# Oldest_Schematic.net
KiCad netlist of a schematic drawn in EAGLE
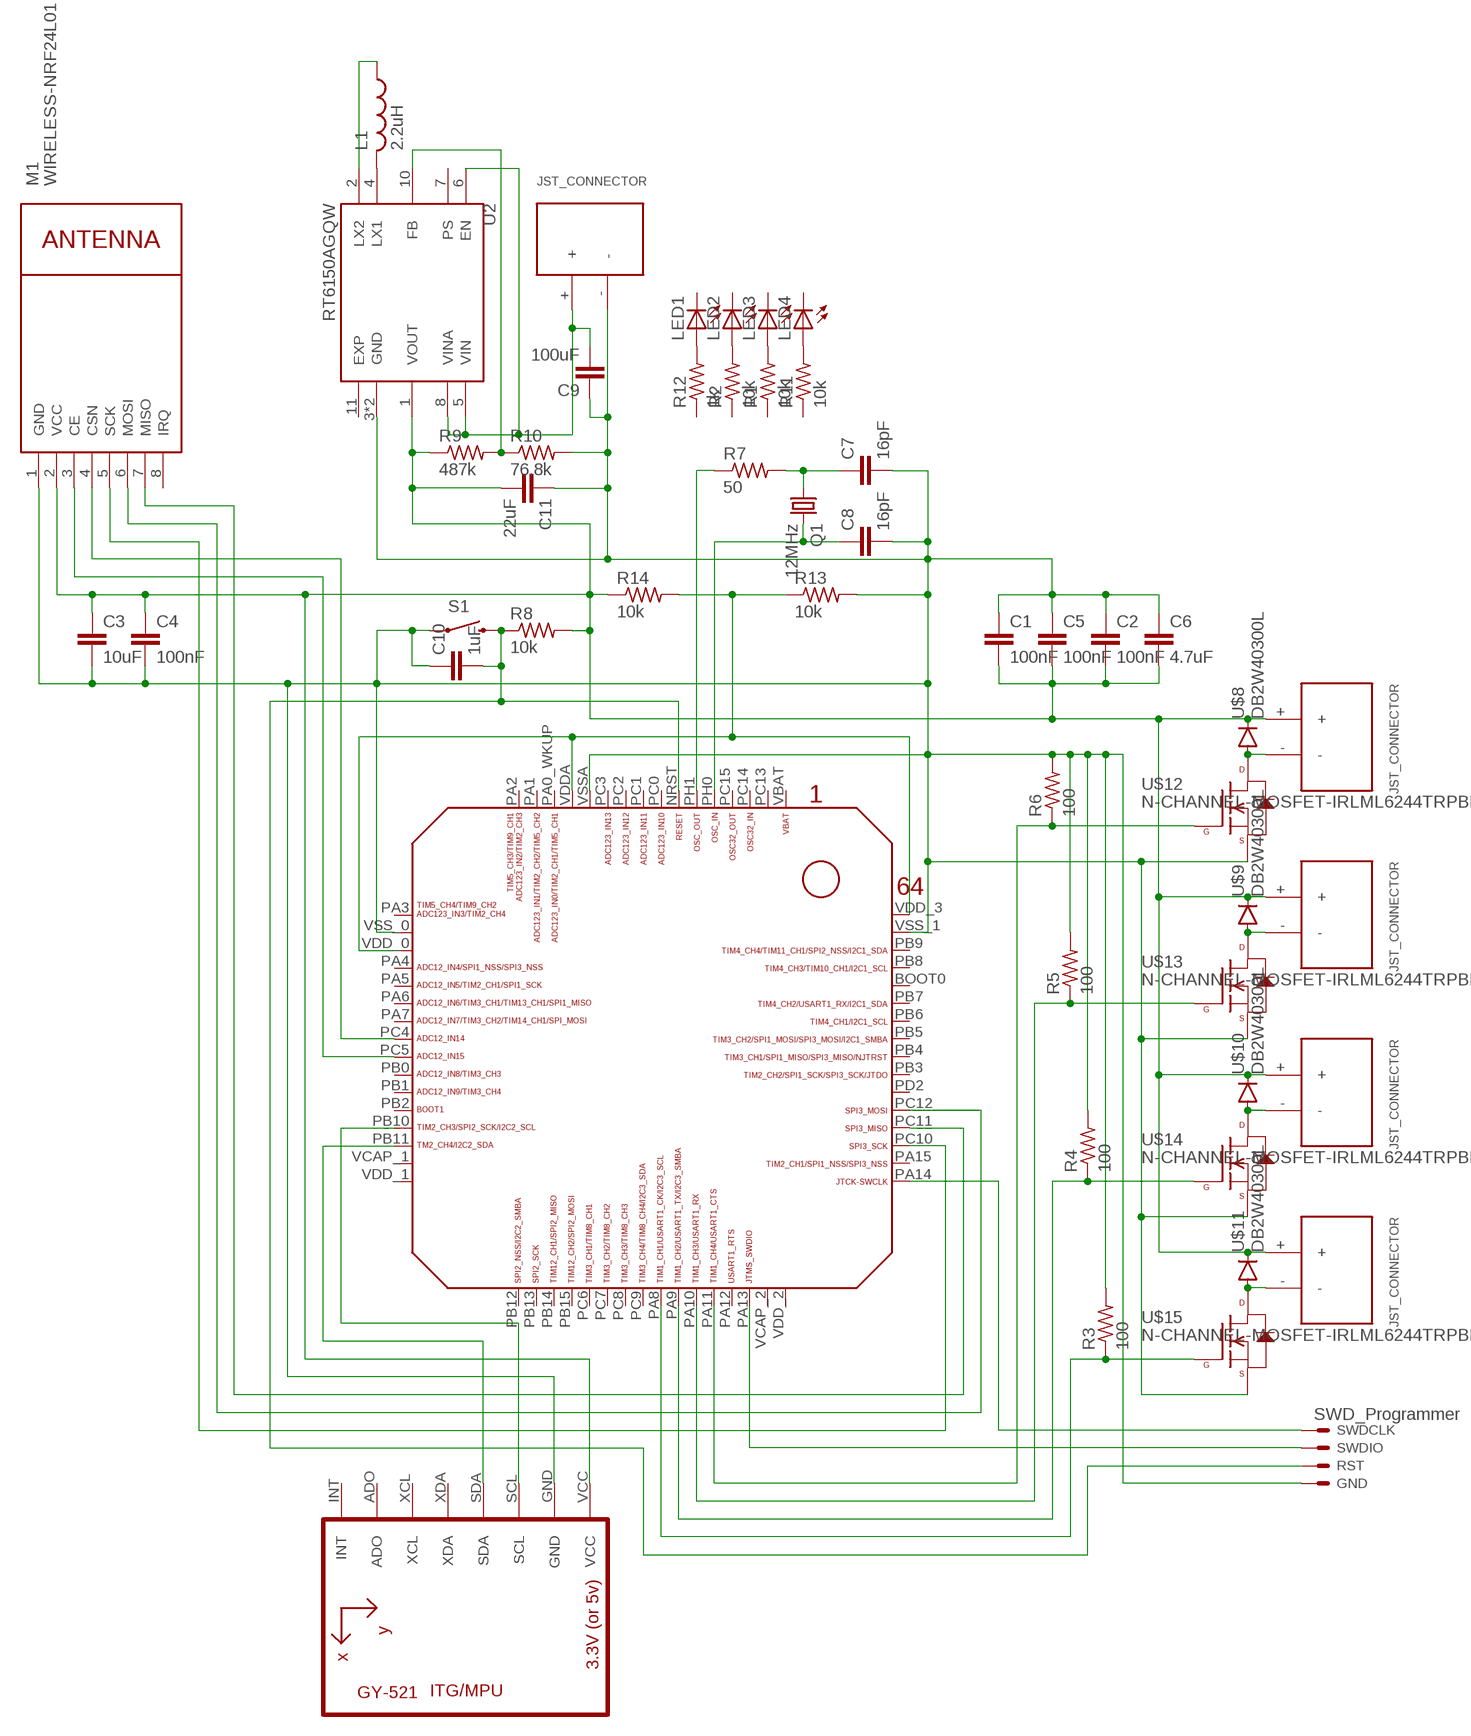
[diagram p0: schematic, sheet 1]

(export (version "E")
  (design (tool "Eeschema 10.0.6"))
  (components
    (comp (ref "C1")
      (value "100nF")
      (footprint "eagle-import:C0603")
      (libsource (lib "eagle-import") (part "C-EUC0603"))
    )
    (comp (ref "C2")
      (value "100nF")
      (footprint "eagle-import:C0603")
      (libsource (lib "eagle-import") (part "C-EUC0603"))
    )
    (comp (ref "C3")
      (value "10uF")
      (footprint "eagle-import:C0603")
      (libsource (lib "eagle-import") (part "C-EUC0603"))
    )
    (comp (ref "C4")
      (value "100nF")
      (footprint "eagle-import:C0603")
      (libsource (lib "eagle-import") (part "C-EUC0603"))
    )
    (comp (ref "C5")
      (value "100nF")
      (footprint "eagle-import:C0603")
      (libsource (lib "eagle-import") (part "C-EUC0603"))
    )
    (comp (ref "C6")
      (value "4.7uF")
      (footprint "eagle-import:C0603")
      (libsource (lib "eagle-import") (part "C-EUC0603"))
    )
    (comp (ref "C7")
      (value "16pF")
      (footprint "eagle-import:C0603")
      (libsource (lib "eagle-import") (part "C-EUC0603"))
    )
    (comp (ref "C8")
      (value "16pF")
      (footprint "eagle-import:C0603")
      (libsource (lib "eagle-import") (part "C-EUC0603"))
    )
    (comp (ref "C9")
      (value "100uF")
      (footprint "eagle-import:C1206")
      (libsource (lib "eagle-import") (part "C-EUC1206"))
    )
    (comp (ref "C10")
      (value "1uF")
      (footprint "eagle-import:C0603")
      (libsource (lib "eagle-import") (part "C-EUC0603"))
    )
    (comp (ref "C11")
      (value "22uF")
      (footprint "eagle-import:C0603")
      (libsource (lib "eagle-import") (part "C-EUC0603"))
    )
    (comp (ref "L1")
      (value "2.2uH")
      (footprint "eagle-import:L0603")
      (libsource (lib "eagle-import") (part "L-USL0603"))
    )
    (comp (ref "LED1")
      (value "LEDSML0603")
      (footprint "eagle-import:SML0603")
      (libsource (lib "eagle-import") (part "LEDSML0603"))
    )
    (comp (ref "LED2")
      (value "LEDSML0603")
      (footprint "eagle-import:SML0603")
      (libsource (lib "eagle-import") (part "LEDSML0603"))
    )
    (comp (ref "LED3")
      (value "LEDSML0603")
      (footprint "eagle-import:SML0603")
      (libsource (lib "eagle-import") (part "LEDSML0603"))
    )
    (comp (ref "LED4")
      (value "LEDSML0603")
      (footprint "eagle-import:SML0603")
      (libsource (lib "eagle-import") (part "LEDSML0603"))
    )
    (comp (ref "M1")
      (value "WIRELESS-NRF24L01")
      (footprint "eagle-import:WIRELESS-NRF24L01")
      (libsource (lib "eagle-import") (part "WIRELESS-NRF24L01"))
    )
    (comp (ref "PIN")
      (value "SWD_Programmer")
      (footprint "eagle-import:53261-04")
      (fields (field (name "MF") "MOLEX"))
      (libsource (lib "eagle-import") (part "53?-04261"))
    )
    (comp (ref "Q1")
      (value "12MHz")
      (footprint "eagle-import:HC49UP")
      (libsource (lib "eagle-import") (part "CRYSTALHC49UP"))
    )
    (comp (ref "R1")
      (value "10k")
      (footprint "eagle-import:R0603")
      (libsource (lib "eagle-import") (part "R-US_R0603"))
    )
    (comp (ref "R2")
      (value "10k")
      (footprint "eagle-import:R0603")
      (libsource (lib "eagle-import") (part "R-US_R0603"))
    )
    (comp (ref "R3")
      (value "100")
      (footprint "eagle-import:R0603")
      (libsource (lib "eagle-import") (part "R-US_R0603"))
    )
    (comp (ref "R4")
      (value "100")
      (footprint "eagle-import:R0603")
      (libsource (lib "eagle-import") (part "R-US_R0603"))
    )
    (comp (ref "R5")
      (value "100")
      (footprint "eagle-import:R0603")
      (libsource (lib "eagle-import") (part "R-US_R0603"))
    )
    (comp (ref "R6")
      (value "100")
      (footprint "eagle-import:R0603")
      (libsource (lib "eagle-import") (part "R-US_R0603"))
    )
    (comp (ref "R7")
      (value "50")
      (footprint "eagle-import:R0603")
      (libsource (lib "eagle-import") (part "R-US_R0603"))
    )
    (comp (ref "R8")
      (value "10k")
      (footprint "eagle-import:R0603")
      (libsource (lib "eagle-import") (part "R-US_R0603"))
    )
    (comp (ref "R9")
      (value "487k")
      (footprint "eagle-import:R0603")
      (libsource (lib "eagle-import") (part "R-US_R0603"))
    )
    (comp (ref "R10")
      (value "76.8k")
      (footprint "eagle-import:R0603")
      (libsource (lib "eagle-import") (part "R-US_R0603"))
    )
    (comp (ref "R11")
      (value "10k")
      (footprint "eagle-import:R0603")
      (libsource (lib "eagle-import") (part "R-US_R0603"))
    )
    (comp (ref "R12")
      (value "1k")
      (footprint "eagle-import:R0603")
      (libsource (lib "eagle-import") (part "R-US_R0603"))
    )
    (comp (ref "R13")
      (value "10k")
      (footprint "eagle-import:R0603")
      (libsource (lib "eagle-import") (part "R-US_R0603"))
    )
    (comp (ref "R14")
      (value "10k")
      (footprint "eagle-import:R0603")
      (libsource (lib "eagle-import") (part "R-US_R0603"))
    )
    (comp (ref "S1")
      (value "SWITCH-MOMENTARY-2SMD")
      (footprint "eagle-import:TACTILE-SWITCH-SMD")
      (libsource (lib "eagle-import") (part "SWITCH-MOMENTARY-2SMD"))
    )
    (comp (ref "U$1")
      (value "STM32F405/415_LQFP64")
      (footprint "eagle-import:STM32F405_415_LQFP64")
      (libsource (lib "eagle-import") (part "STM32F405/415_LQFP64"))
    )
    (comp (ref "U$2")
      (value "JST_CONNECTOR_FEMALE")
      (footprint "eagle-import:JST_CONNECTOR_FEMALE")
      (libsource (lib "eagle-import") (part "JST_CONNECTOR_FEMALE"))
    )
    (comp (ref "U$4")
      (value "JST_CONNECTOR_FEMALE")
      (footprint "eagle-import:JST_CONNECTOR_FEMALE")
      (libsource (lib "eagle-import") (part "JST_CONNECTOR_FEMALE"))
    )
    (comp (ref "U$5")
      (value "JST_CONNECTOR_FEMALE")
      (footprint "eagle-import:JST_CONNECTOR_FEMALE")
      (libsource (lib "eagle-import") (part "JST_CONNECTOR_FEMALE"))
    )
    (comp (ref "U$6")
      (value "JST_CONNECTOR_FEMALE")
      (footprint "eagle-import:JST_CONNECTOR_FEMALE")
      (libsource (lib "eagle-import") (part "JST_CONNECTOR_FEMALE"))
    )
    (comp (ref "U$7")
      (value "JST_CONNECTOR_FEMALE")
      (footprint "eagle-import:JST_CONNECTOR_FEMALE")
      (libsource (lib "eagle-import") (part "JST_CONNECTOR_FEMALE"))
    )
    (comp (ref "U$8")
      (value "DB2W40300L")
      (footprint "eagle-import:MINI2-F3-B")
      (libsource (lib "eagle-import") (part "DB2W40300L"))
    )
    (comp (ref "U$9")
      (value "DB2W40300L")
      (footprint "eagle-import:MINI2-F3-B")
      (libsource (lib "eagle-import") (part "DB2W40300L"))
    )
    (comp (ref "U$10")
      (value "DB2W40300L")
      (footprint "eagle-import:MINI2-F3-B")
      (libsource (lib "eagle-import") (part "DB2W40300L"))
    )
    (comp (ref "U$11")
      (value "DB2W40300L")
      (footprint "eagle-import:MINI2-F3-B")
      (libsource (lib "eagle-import") (part "DB2W40300L"))
    )
    (comp (ref "U$12")
      (value "N-CHANNEL-MOSFET-IRLML6244TRPBF")
      (footprint "eagle-import:SOT23-3")
      (libsource (lib "eagle-import") (part "N-CHANNEL-MOSFET-IRLML6244TRPBF"))
    )
    (comp (ref "U$13")
      (value "N-CHANNEL-MOSFET-IRLML6244TRPBF")
      (footprint "eagle-import:SOT23-3")
      (libsource (lib "eagle-import") (part "N-CHANNEL-MOSFET-IRLML6244TRPBF"))
    )
    (comp (ref "U$14")
      (value "N-CHANNEL-MOSFET-IRLML6244TRPBF")
      (footprint "eagle-import:SOT23-3")
      (libsource (lib "eagle-import") (part "N-CHANNEL-MOSFET-IRLML6244TRPBF"))
    )
    (comp (ref "U$15")
      (value "N-CHANNEL-MOSFET-IRLML6244TRPBF")
      (footprint "eagle-import:SOT23-3")
      (libsource (lib "eagle-import") (part "N-CHANNEL-MOSFET-IRLML6244TRPBF"))
    )
    (comp (ref "U1")
      (value "GY-521MPU6050")
      (footprint "eagle-import:GY-521")
      (libsource (lib "eagle-import") (part "GY-521MPU6050"))
    )
    (comp (ref "U2")
      (value "RT6150AGQW")
      (footprint "eagle-import:SON50P250X250X80-11N")
      (fields (field (name "MF") "Richtek USA"))
      (libsource (lib "eagle-import") (part "RT6150AGQW"))
    )
  )
  (nets
    (net (code "1") (name "Net-(C7-Pad1)") (class "Default")
      (node (ref "C7") (pin "1") (pinfunction "1_1") (pintype "passive"))
      (node (ref "Q1") (pin "1") (pinfunction "1_1") (pintype "passive"))
      (node (ref "R7") (pin "2") (pinfunction "2_2") (pintype "passive"))
    )
    (net (code "2") (name "Net-(C8-Pad1)") (class "Default")
      (node (ref "C8") (pin "1") (pinfunction "1_1") (pintype "passive"))
      (node (ref "Q1") (pin "2") (pinfunction "2_2") (pintype "passive"))
      (node (ref "U$1") (pin "PH0") (pinfunction "PH0_PH0") (pintype "bidirectional"))
    )
    (net (code "3") (name "Net-(LED1-PadA)") (class "Default")
      (node (ref "LED1") (pin "A") (pinfunction "A_A") (pintype "passive"))
      (node (ref "R12") (pin "2") (pinfunction "2_2") (pintype "passive"))
    )
    (net (code "4") (name "Net-(LED2-PadA)") (class "Default")
      (node (ref "LED2") (pin "A") (pinfunction "A_A") (pintype "passive"))
      (node (ref "R2") (pin "2") (pinfunction "2_2") (pintype "passive"))
    )
    (net (code "5") (name "Net-(LED3-PadA)") (class "Default")
      (node (ref "LED3") (pin "A") (pinfunction "A_A") (pintype "passive"))
      (node (ref "R1") (pin "2") (pinfunction "2_2") (pintype "passive"))
    )
    (net (code "6") (name "Net-(LED4-PadA)") (class "Default")
      (node (ref "LED4") (pin "A") (pinfunction "A_A") (pintype "passive"))
      (node (ref "R11") (pin "2") (pinfunction "2_2") (pintype "passive"))
    )
    (net (code "7") (name "Net-(M1-CE)") (class "Default")
      (node (ref "M1") (pin "3") (pinfunction "CE_3") (pintype "bidirectional"))
      (node (ref "U$1") (pin "PC5") (pinfunction "PC5_PC5") (pintype "bidirectional"))
    )
    (net (code "8") (name "Net-(M1-CSN)") (class "Default")
      (node (ref "M1") (pin "4") (pinfunction "CSN_4") (pintype "bidirectional"))
      (node (ref "U$1") (pin "PC4") (pinfunction "PC4_PC4") (pintype "bidirectional"))
    )
    (net (code "9") (name "Net-(M1-GND)") (class "Default")
      (node (ref "C1") (pin "1") (pinfunction "1_1") (pintype "passive"))
      (node (ref "C10") (pin "1") (pinfunction "1_1") (pintype "passive"))
      (node (ref "C11") (pin "1") (pinfunction "1_1") (pintype "passive"))
      (node (ref "C2") (pin "1") (pinfunction "1_1") (pintype "passive"))
      (node (ref "C3") (pin "2") (pinfunction "2_2") (pintype "passive"))
      (node (ref "C4") (pin "2") (pinfunction "2_2") (pintype "passive"))
      (node (ref "C5") (pin "1") (pinfunction "1_1") (pintype "passive"))
      (node (ref "C6") (pin "1") (pinfunction "1_1") (pintype "passive"))
      (node (ref "C7") (pin "2") (pinfunction "2_2") (pintype "passive"))
      (node (ref "C8") (pin "2") (pinfunction "2_2") (pintype "passive"))
      (node (ref "C9") (pin "1") (pinfunction "1_1") (pintype "passive"))
      (node (ref "M1") (pin "1") (pinfunction "GND_1") (pintype "power_in"))
      (node (ref "PIN") (pin "4") (pinfunction "S_4") (pintype "passive"))
      (node (ref "R10") (pin "2") (pinfunction "2_2") (pintype "passive"))
      (node (ref "R13") (pin "2") (pinfunction "2_2") (pintype "passive"))
      (node (ref "R3") (pin "2") (pinfunction "2_2") (pintype "passive"))
      (node (ref "R4") (pin "2") (pinfunction "2_2") (pintype "passive"))
      (node (ref "R5") (pin "2") (pinfunction "2_2") (pintype "passive"))
      (node (ref "R6") (pin "2") (pinfunction "2_2") (pintype "passive"))
      (node (ref "S1") (pin "1") (pinfunction "1_1") (pintype "passive"))
      (node (ref "U$1") (pin "VSSA") (pinfunction "VSSA_VSSA") (pintype "bidirectional"))
      (node (ref "U$1") (pin "VSS_0") (pinfunction "VSS_0_VSS_0") (pintype "bidirectional"))
      (node (ref "U$1") (pin "VSS_1") (pinfunction "VSS_1_VSS_1") (pintype "bidirectional"))
      (node (ref "U$12") (pin "2") (pinfunction "S_2") (pintype "passive"))
      (node (ref "U$13") (pin "2") (pinfunction "S_2") (pintype "passive"))
      (node (ref "U$14") (pin "2") (pinfunction "S_2") (pintype "passive"))
      (node (ref "U$15") (pin "2") (pinfunction "S_2") (pintype "passive"))
      (node (ref "U$2") (pin "-") (pinfunction "-_-") (pintype "bidirectional"))
      (node (ref "U1") (pin "GND") (pinfunction "GND_GND") (pintype "bidirectional"))
      (node (ref "U2") (pin "3") (pinfunction "GND_3") (pintype "power_in"))
      (node (ref "U2") (pin "9") (pinfunction "GND_9") (pintype "power_in"))
    )
    (net (code "10") (name "Net-(M1-MISO)") (class "Default")
      (node (ref "M1") (pin "7") (pinfunction "MISO_7") (pintype "bidirectional"))
      (node (ref "U$1") (pin "PC11") (pinfunction "PC11_PC11") (pintype "bidirectional"))
    )
    (net (code "11") (name "Net-(M1-MOSI)") (class "Default")
      (node (ref "M1") (pin "6") (pinfunction "MOSI_6") (pintype "bidirectional"))
      (node (ref "U$1") (pin "PC12") (pinfunction "PC12_PC12") (pintype "bidirectional"))
    )
    (net (code "12") (name "Net-(M1-SCK)") (class "Default")
      (node (ref "M1") (pin "5") (pinfunction "SCK_5") (pintype "bidirectional"))
      (node (ref "U$1") (pin "PC10") (pinfunction "PC10_PC10") (pintype "bidirectional"))
    )
    (net (code "13") (name "Net-(M1-VCC)") (class "Default")
      (node (ref "C1") (pin "2") (pinfunction "2_2") (pintype "passive"))
      (node (ref "C11") (pin "2") (pinfunction "2_2") (pintype "passive"))
      (node (ref "C2") (pin "2") (pinfunction "2_2") (pintype "passive"))
      (node (ref "C3") (pin "1") (pinfunction "1_1") (pintype "passive"))
      (node (ref "C4") (pin "1") (pinfunction "1_1") (pintype "passive"))
      (node (ref "C5") (pin "2") (pinfunction "2_2") (pintype "passive"))
      (node (ref "C6") (pin "2") (pinfunction "2_2") (pintype "passive"))
      (node (ref "M1") (pin "2") (pinfunction "VCC_2") (pintype "power_in"))
      (node (ref "R14") (pin "1") (pinfunction "1_1") (pintype "passive"))
      (node (ref "R8") (pin "2") (pinfunction "2_2") (pintype "passive"))
      (node (ref "R9") (pin "1") (pinfunction "1_1") (pintype "passive"))
      (node (ref "U$10") (pin "NEG") (pinfunction "GPIN_NEG") (pintype "passive"))
      (node (ref "U$11") (pin "NEG") (pinfunction "GPIN_NEG") (pintype "passive"))
      (node (ref "U$4") (pin "+") (pinfunction "+_+") (pintype "bidirectional"))
      (node (ref "U$5") (pin "+") (pinfunction "+_+") (pintype "bidirectional"))
      (node (ref "U$6") (pin "+") (pinfunction "+_+") (pintype "bidirectional"))
      (node (ref "U$7") (pin "+") (pinfunction "+_+") (pintype "bidirectional"))
      (node (ref "U$8") (pin "NEG") (pinfunction "GPIN_NEG") (pintype "passive"))
      (node (ref "U$9") (pin "NEG") (pinfunction "GPIN_NEG") (pintype "passive"))
      (node (ref "U1") (pin "VCC") (pinfunction "VCC_VCC") (pintype "bidirectional"))
      (node (ref "U2") (pin "1") (pinfunction "VOUT_1") (pintype "output"))
    )
    (net (code "14") (name "Net-(PINA-S)") (class "Default")
      (node (ref "PIN") (pin "1") (pinfunction "S_1") (pintype "passive"))
      (node (ref "U$1") (pin "PA14") (pinfunction "PA14_PA14") (pintype "bidirectional"))
    )
    (net (code "15") (name "Net-(PINB-S)") (class "Default")
      (node (ref "PIN") (pin "2") (pinfunction "S_2") (pintype "passive"))
      (node (ref "U$1") (pin "PA13") (pinfunction "PA13_PA13") (pintype "bidirectional"))
    )
    (net (code "16") (name "Net-(PINC-S)") (class "Default")
      (node (ref "C10") (pin "2") (pinfunction "2_2") (pintype "passive"))
      (node (ref "PIN") (pin "3") (pinfunction "S_3") (pintype "passive"))
      (node (ref "R8") (pin "1") (pinfunction "1_1") (pintype "passive"))
      (node (ref "S1") (pin "3") (pinfunction "2_3") (pintype "passive"))
      (node (ref "U$1") (pin "NRST") (pinfunction "NRST_NRST") (pintype "bidirectional"))
    )
    (net (code "17") (name "Net-(R7-Pad1)") (class "Default")
      (node (ref "R7") (pin "1") (pinfunction "1_1") (pintype "passive"))
      (node (ref "U$1") (pin "PH1") (pinfunction "PH1_PH1") (pintype "bidirectional"))
    )
    (net (code "18") (name "Net-(R13-Pad1)") (class "Default")
      (node (ref "R13") (pin "1") (pinfunction "1_1") (pintype "passive"))
      (node (ref "R14") (pin "2") (pinfunction "2_2") (pintype "passive"))
      (node (ref "U$1") (pin "VDDA") (pinfunction "VDDA_VDDA") (pintype "bidirectional"))
      (node (ref "U$1") (pin "VDD_0") (pinfunction "VDD_0_VDD_0") (pintype "bidirectional"))
      (node (ref "U$1") (pin "VDD_3") (pinfunction "VDD_3_VDD_3") (pintype "bidirectional"))
    )
    (net (code "19") (name "Net-(U$1-PadPB10)") (class "Default")
      (node (ref "U$1") (pin "PB10") (pinfunction "PB10_PB10") (pintype "bidirectional"))
      (node (ref "U1") (pin "SCL") (pinfunction "SCL_SCL") (pintype "bidirectional"))
    )
    (net (code "20") (name "Net-(U$1-PadPB11)") (class "Default")
      (node (ref "U$1") (pin "PB11") (pinfunction "PB11_PB11") (pintype "bidirectional"))
      (node (ref "U1") (pin "SDA") (pinfunction "SDA_SDA") (pintype "bidirectional"))
    )
    (net (code "21") (name "Net-(U$10-PPIN)") (class "Default")
      (node (ref "U$10") (pin "POS") (pinfunction "PPIN_POS") (pintype "passive"))
      (node (ref "U$14") (pin "3") (pinfunction "D_3") (pintype "passive"))
      (node (ref "U$6") (pin "-") (pinfunction "-_-") (pintype "bidirectional"))
    )
    (net (code "22") (name "Net-(U$11-PPIN)") (class "Default")
      (node (ref "U$11") (pin "POS") (pinfunction "PPIN_POS") (pintype "passive"))
      (node (ref "U$15") (pin "3") (pinfunction "D_3") (pintype "passive"))
      (node (ref "U$7") (pin "-") (pinfunction "-_-") (pintype "bidirectional"))
    )
    (net (code "23") (name "Net-(U$12-D)") (class "Default")
      (node (ref "U$12") (pin "3") (pinfunction "D_3") (pintype "passive"))
      (node (ref "U$4") (pin "-") (pinfunction "-_-") (pintype "bidirectional"))
      (node (ref "U$8") (pin "POS") (pinfunction "PPIN_POS") (pintype "passive"))
    )
    (net (code "24") (name "Net-(U$12-G)") (class "Default")
      (node (ref "R6") (pin "1") (pinfunction "1_1") (pintype "passive"))
      (node (ref "U$1") (pin "PA11") (pinfunction "PA11_PA11") (pintype "bidirectional"))
      (node (ref "U$12") (pin "1") (pinfunction "G_1") (pintype "passive"))
    )
    (net (code "25") (name "Net-(U$13-D)") (class "Default")
      (node (ref "U$13") (pin "3") (pinfunction "D_3") (pintype "passive"))
      (node (ref "U$5") (pin "-") (pinfunction "-_-") (pintype "bidirectional"))
      (node (ref "U$9") (pin "POS") (pinfunction "PPIN_POS") (pintype "passive"))
    )
    (net (code "26") (name "Net-(U$13-G)") (class "Default")
      (node (ref "R5") (pin "1") (pinfunction "1_1") (pintype "passive"))
      (node (ref "U$1") (pin "PA10") (pinfunction "PA10_PA10") (pintype "bidirectional"))
      (node (ref "U$13") (pin "1") (pinfunction "G_1") (pintype "passive"))
    )
    (net (code "27") (name "Net-(U$14-G)") (class "Default")
      (node (ref "R4") (pin "1") (pinfunction "1_1") (pintype "passive"))
      (node (ref "U$1") (pin "PA9") (pinfunction "PA9_PA9") (pintype "bidirectional"))
      (node (ref "U$14") (pin "1") (pinfunction "G_1") (pintype "passive"))
    )
    (net (code "28") (name "Net-(U$15-G)") (class "Default")
      (node (ref "R3") (pin "1") (pinfunction "1_1") (pintype "passive"))
      (node (ref "U$1") (pin "PA8") (pinfunction "PA8_PA8") (pintype "bidirectional"))
      (node (ref "U$15") (pin "1") (pinfunction "G_1") (pintype "passive"))
    )
    (net (code "29") (name "Net-(U2-EN)") (class "Default")
      (node (ref "C9") (pin "2") (pinfunction "2_2") (pintype "passive"))
      (node (ref "U$2") (pin "+") (pinfunction "+_+") (pintype "bidirectional"))
      (node (ref "U2") (pin "5") (pinfunction "VIN_5") (pintype "power_in"))
      (node (ref "U2") (pin "6") (pinfunction "EN_6") (pintype "input"))
      (node (ref "U2") (pin "8") (pinfunction "VINA_8") (pintype "power_in"))
    )
    (net (code "30") (name "Net-(U2-FB)") (class "Default")
      (node (ref "R10") (pin "1") (pinfunction "1_1") (pintype "passive"))
      (node (ref "R9") (pin "2") (pinfunction "2_2") (pintype "passive"))
      (node (ref "U2") (pin "10") (pinfunction "FB_10") (pintype "input"))
    )
    (net (code "31") (name "Net-(U2-LX1)") (class "Default")
      (node (ref "L1") (pin "2") (pinfunction "2_2") (pintype "passive"))
      (node (ref "U2") (pin "4") (pinfunction "LX1_4") (pintype "passive"))
    )
    (net (code "32") (name "Net-(U2-LX2)") (class "Default")
      (node (ref "L1") (pin "1") (pinfunction "1_1") (pintype "passive"))
      (node (ref "U2") (pin "2") (pinfunction "LX2_2") (pintype "passive"))
    )
    (net (code "33") (name "unconnected-(LED1-PadC)") (class "Default")
      (node (ref "LED1") (pin "C") (pinfunction "C_C") (pintype "passive"))
    )
    (net (code "34") (name "unconnected-(LED2-PadC)") (class "Default")
      (node (ref "LED2") (pin "C") (pinfunction "C_C") (pintype "passive"))
    )
    (net (code "35") (name "unconnected-(LED3-PadC)") (class "Default")
      (node (ref "LED3") (pin "C") (pinfunction "C_C") (pintype "passive"))
    )
    (net (code "36") (name "unconnected-(LED4-PadC)") (class "Default")
      (node (ref "LED4") (pin "C") (pinfunction "C_C") (pintype "passive"))
    )
    (net (code "37") (name "unconnected-(M1-IRQ-Pad8)") (class "Default")
      (node (ref "M1") (pin "8") (pinfunction "IRQ_8") (pintype "bidirectional"))
    )
    (net (code "38") (name "unconnected-(R1-Pad1)") (class "Default")
      (node (ref "R1") (pin "1") (pinfunction "1_1") (pintype "passive"))
    )
    (net (code "39") (name "unconnected-(R2-Pad1)") (class "Default")
      (node (ref "R2") (pin "1") (pinfunction "1_1") (pintype "passive"))
    )
    (net (code "40") (name "unconnected-(R11-Pad1)") (class "Default")
      (node (ref "R11") (pin "1") (pinfunction "1_1") (pintype "passive"))
    )
    (net (code "41") (name "unconnected-(R12-Pad1)") (class "Default")
      (node (ref "R12") (pin "1") (pinfunction "1_1") (pintype "passive"))
    )
    (net (code "42") (name "unconnected-(U$1-PA0_AKUP-PadPA0_WKUP)") (class "Default")
      (node (ref "U$1") (pin "PA0_WKUP") (pinfunction "PA0_AKUP_PA0_WKUP") (pintype "bidirectional"))
    )
    (net (code "43") (name "unconnected-(U$1-PadBOOT0)") (class "Default")
      (node (ref "U$1") (pin "BOOT0") (pinfunction "BOOT0_BOOT0") (pintype "bidirectional"))
    )
    (net (code "44") (name "unconnected-(U$1-PadPA1)") (class "Default")
      (node (ref "U$1") (pin "PA1") (pinfunction "PA1_PA1") (pintype "bidirectional"))
    )
    (net (code "45") (name "unconnected-(U$1-PadPA2)") (class "Default")
      (node (ref "U$1") (pin "PA2") (pinfunction "PA2_PA2") (pintype "bidirectional"))
    )
    (net (code "46") (name "unconnected-(U$1-PadPA3)") (class "Default")
      (node (ref "U$1") (pin "PA3") (pinfunction "PA3_PA3") (pintype "bidirectional"))
    )
    (net (code "47") (name "unconnected-(U$1-PadPA4)") (class "Default")
      (node (ref "U$1") (pin "PA4") (pinfunction "PA4_PA4") (pintype "bidirectional"))
    )
    (net (code "48") (name "unconnected-(U$1-PadPA5)") (class "Default")
      (node (ref "U$1") (pin "PA5") (pinfunction "PA5_PA5") (pintype "bidirectional"))
    )
    (net (code "49") (name "unconnected-(U$1-PadPA6)") (class "Default")
      (node (ref "U$1") (pin "PA6") (pinfunction "PA6_PA6") (pintype "bidirectional"))
    )
    (net (code "50") (name "unconnected-(U$1-PadPA7)") (class "Default")
      (node (ref "U$1") (pin "PA7") (pinfunction "PA7_PA7") (pintype "bidirectional"))
    )
    (net (code "51") (name "unconnected-(U$1-PadPA12)") (class "Default")
      (node (ref "U$1") (pin "PA12") (pinfunction "PA12_PA12") (pintype "bidirectional"))
    )
    (net (code "52") (name "unconnected-(U$1-PadPA15)") (class "Default")
      (node (ref "U$1") (pin "PA15") (pinfunction "PA15_PA15") (pintype "bidirectional"))
    )
    (net (code "53") (name "unconnected-(U$1-PadPB0)") (class "Default")
      (node (ref "U$1") (pin "PB0") (pinfunction "PB0_PB0") (pintype "bidirectional"))
    )
    (net (code "54") (name "unconnected-(U$1-PadPB1)") (class "Default")
      (node (ref "U$1") (pin "PB1") (pinfunction "PB1_PB1") (pintype "bidirectional"))
    )
    (net (code "55") (name "unconnected-(U$1-PadPB2)") (class "Default")
      (node (ref "U$1") (pin "PB2") (pinfunction "PB2_PB2") (pintype "bidirectional"))
    )
    (net (code "56") (name "unconnected-(U$1-PadPB3)") (class "Default")
      (node (ref "U$1") (pin "PB3") (pinfunction "PB3_PB3") (pintype "bidirectional"))
    )
    (net (code "57") (name "unconnected-(U$1-PadPB4)") (class "Default")
      (node (ref "U$1") (pin "PB4") (pinfunction "PB4_PB4") (pintype "bidirectional"))
    )
    (net (code "58") (name "unconnected-(U$1-PadPB5)") (class "Default")
      (node (ref "U$1") (pin "PB5") (pinfunction "PB5_PB5") (pintype "bidirectional"))
    )
    (net (code "59") (name "unconnected-(U$1-PadPB6)") (class "Default")
      (node (ref "U$1") (pin "PB6") (pinfunction "PB6_PB6") (pintype "bidirectional"))
    )
    (net (code "60") (name "unconnected-(U$1-PadPB7)") (class "Default")
      (node (ref "U$1") (pin "PB7") (pinfunction "PB7_PB7") (pintype "bidirectional"))
    )
    (net (code "61") (name "unconnected-(U$1-PadPB8)") (class "Default")
      (node (ref "U$1") (pin "PB8") (pinfunction "PB8_PB8") (pintype "bidirectional"))
    )
    (net (code "62") (name "unconnected-(U$1-PadPB9)") (class "Default")
      (node (ref "U$1") (pin "PB9") (pinfunction "PB9_PB9") (pintype "bidirectional"))
    )
    (net (code "63") (name "unconnected-(U$1-PadPB12)") (class "Default")
      (node (ref "U$1") (pin "PB12") (pinfunction "PB12_PB12") (pintype "bidirectional"))
    )
    (net (code "64") (name "unconnected-(U$1-PadPB13)") (class "Default")
      (node (ref "U$1") (pin "PB13") (pinfunction "PB13_PB13") (pintype "bidirectional"))
    )
    (net (code "65") (name "unconnected-(U$1-PadPB14)") (class "Default")
      (node (ref "U$1") (pin "PB14") (pinfunction "PB14_PB14") (pintype "bidirectional"))
    )
    (net (code "66") (name "unconnected-(U$1-PadPB15)") (class "Default")
      (node (ref "U$1") (pin "PB15") (pinfunction "PB15_PB15") (pintype "bidirectional"))
    )
    (net (code "67") (name "unconnected-(U$1-PadPC0)") (class "Default")
      (node (ref "U$1") (pin "PC0") (pinfunction "PC0_PC0") (pintype "bidirectional"))
    )
    (net (code "68") (name "unconnected-(U$1-PadPC1)") (class "Default")
      (node (ref "U$1") (pin "PC1") (pinfunction "PC1_PC1") (pintype "bidirectional"))
    )
    (net (code "69") (name "unconnected-(U$1-PadPC2)") (class "Default")
      (node (ref "U$1") (pin "PC2") (pinfunction "PC2_PC2") (pintype "bidirectional"))
    )
    (net (code "70") (name "unconnected-(U$1-PadPC3)") (class "Default")
      (node (ref "U$1") (pin "PC3") (pinfunction "PC3_PC3") (pintype "bidirectional"))
    )
    (net (code "71") (name "unconnected-(U$1-PadPC6)") (class "Default")
      (node (ref "U$1") (pin "PC6") (pinfunction "PC6_PC6") (pintype "bidirectional"))
    )
    (net (code "72") (name "unconnected-(U$1-PadPC7)") (class "Default")
      (node (ref "U$1") (pin "PC7") (pinfunction "PC7_PC7") (pintype "bidirectional"))
    )
    (net (code "73") (name "unconnected-(U$1-PadPC8)") (class "Default")
      (node (ref "U$1") (pin "PC8") (pinfunction "PC8_PC8") (pintype "bidirectional"))
    )
    (net (code "74") (name "unconnected-(U$1-PadPC9)") (class "Default")
      (node (ref "U$1") (pin "PC9") (pinfunction "PC9_PC9") (pintype "bidirectional"))
    )
    (net (code "75") (name "unconnected-(U$1-PadPC13)") (class "Default")
      (node (ref "U$1") (pin "PC13") (pinfunction "PC13_PC13") (pintype "bidirectional"))
    )
    (net (code "76") (name "unconnected-(U$1-PadPC14)") (class "Default")
      (node (ref "U$1") (pin "PC14") (pinfunction "PC14_PC14") (pintype "bidirectional"))
    )
    (net (code "77") (name "unconnected-(U$1-PadPC15)") (class "Default")
      (node (ref "U$1") (pin "PC15") (pinfunction "PC15_PC15") (pintype "bidirectional"))
    )
    (net (code "78") (name "unconnected-(U$1-PadPD2)") (class "Default")
      (node (ref "U$1") (pin "PD2") (pinfunction "PD2_PD2") (pintype "bidirectional"))
    )
    (net (code "79") (name "unconnected-(U$1-PadVBAT)") (class "Default")
      (node (ref "U$1") (pin "VBAT") (pinfunction "VBAT_VBAT") (pintype "bidirectional"))
    )
    (net (code "80") (name "unconnected-(U$1-PadVCAP_1)") (class "Default")
      (node (ref "U$1") (pin "VCAP_1") (pinfunction "VCAP_1_VCAP_1") (pintype "bidirectional"))
    )
    (net (code "81") (name "unconnected-(U$1-PadVCAP_2)") (class "Default")
      (node (ref "U$1") (pin "VCAP_2") (pinfunction "VCAP_2_VCAP_2") (pintype "bidirectional"))
    )
    (net (code "82") (name "unconnected-(U$1-PadVDD_1)") (class "Default")
      (node (ref "U$1") (pin "VDD_1") (pinfunction "VDD_1_VDD_1") (pintype "bidirectional"))
    )
    (net (code "83") (name "unconnected-(U$1-PadVDD_2)") (class "Default")
      (node (ref "U$1") (pin "VDD_2") (pinfunction "VDD_2_VDD_2") (pintype "bidirectional"))
    )
    (net (code "84") (name "unconnected-(U1-PadADO)") (class "Default")
      (node (ref "U1") (pin "ADO") (pinfunction "ADO_ADO") (pintype "bidirectional"))
    )
    (net (code "85") (name "unconnected-(U1-PadINT)") (class "Default")
      (node (ref "U1") (pin "INT") (pinfunction "INT_INT") (pintype "bidirectional"))
    )
    (net (code "86") (name "unconnected-(U1-PadXCL)") (class "Default")
      (node (ref "U1") (pin "XCL") (pinfunction "XCL_XCL") (pintype "bidirectional"))
    )
    (net (code "87") (name "unconnected-(U1-PadXDA)") (class "Default")
      (node (ref "U1") (pin "XDA") (pinfunction "XDA_XDA") (pintype "bidirectional"))
    )
    (net (code "88") (name "unconnected-(U2-EXP-Pad11)") (class "Default")
      (node (ref "U2") (pin "11") (pinfunction "EXP_11") (pintype "passive"))
    )
    (net (code "89") (name "unconnected-(U2-PS-Pad7)") (class "Default")
      (node (ref "U2") (pin "7") (pinfunction "PS_7") (pintype "input"))
    )
  )
)
